# RFCS-RJ45_Foot_Pedal.net
KiCad netlist of a schematic drawn in EAGLE
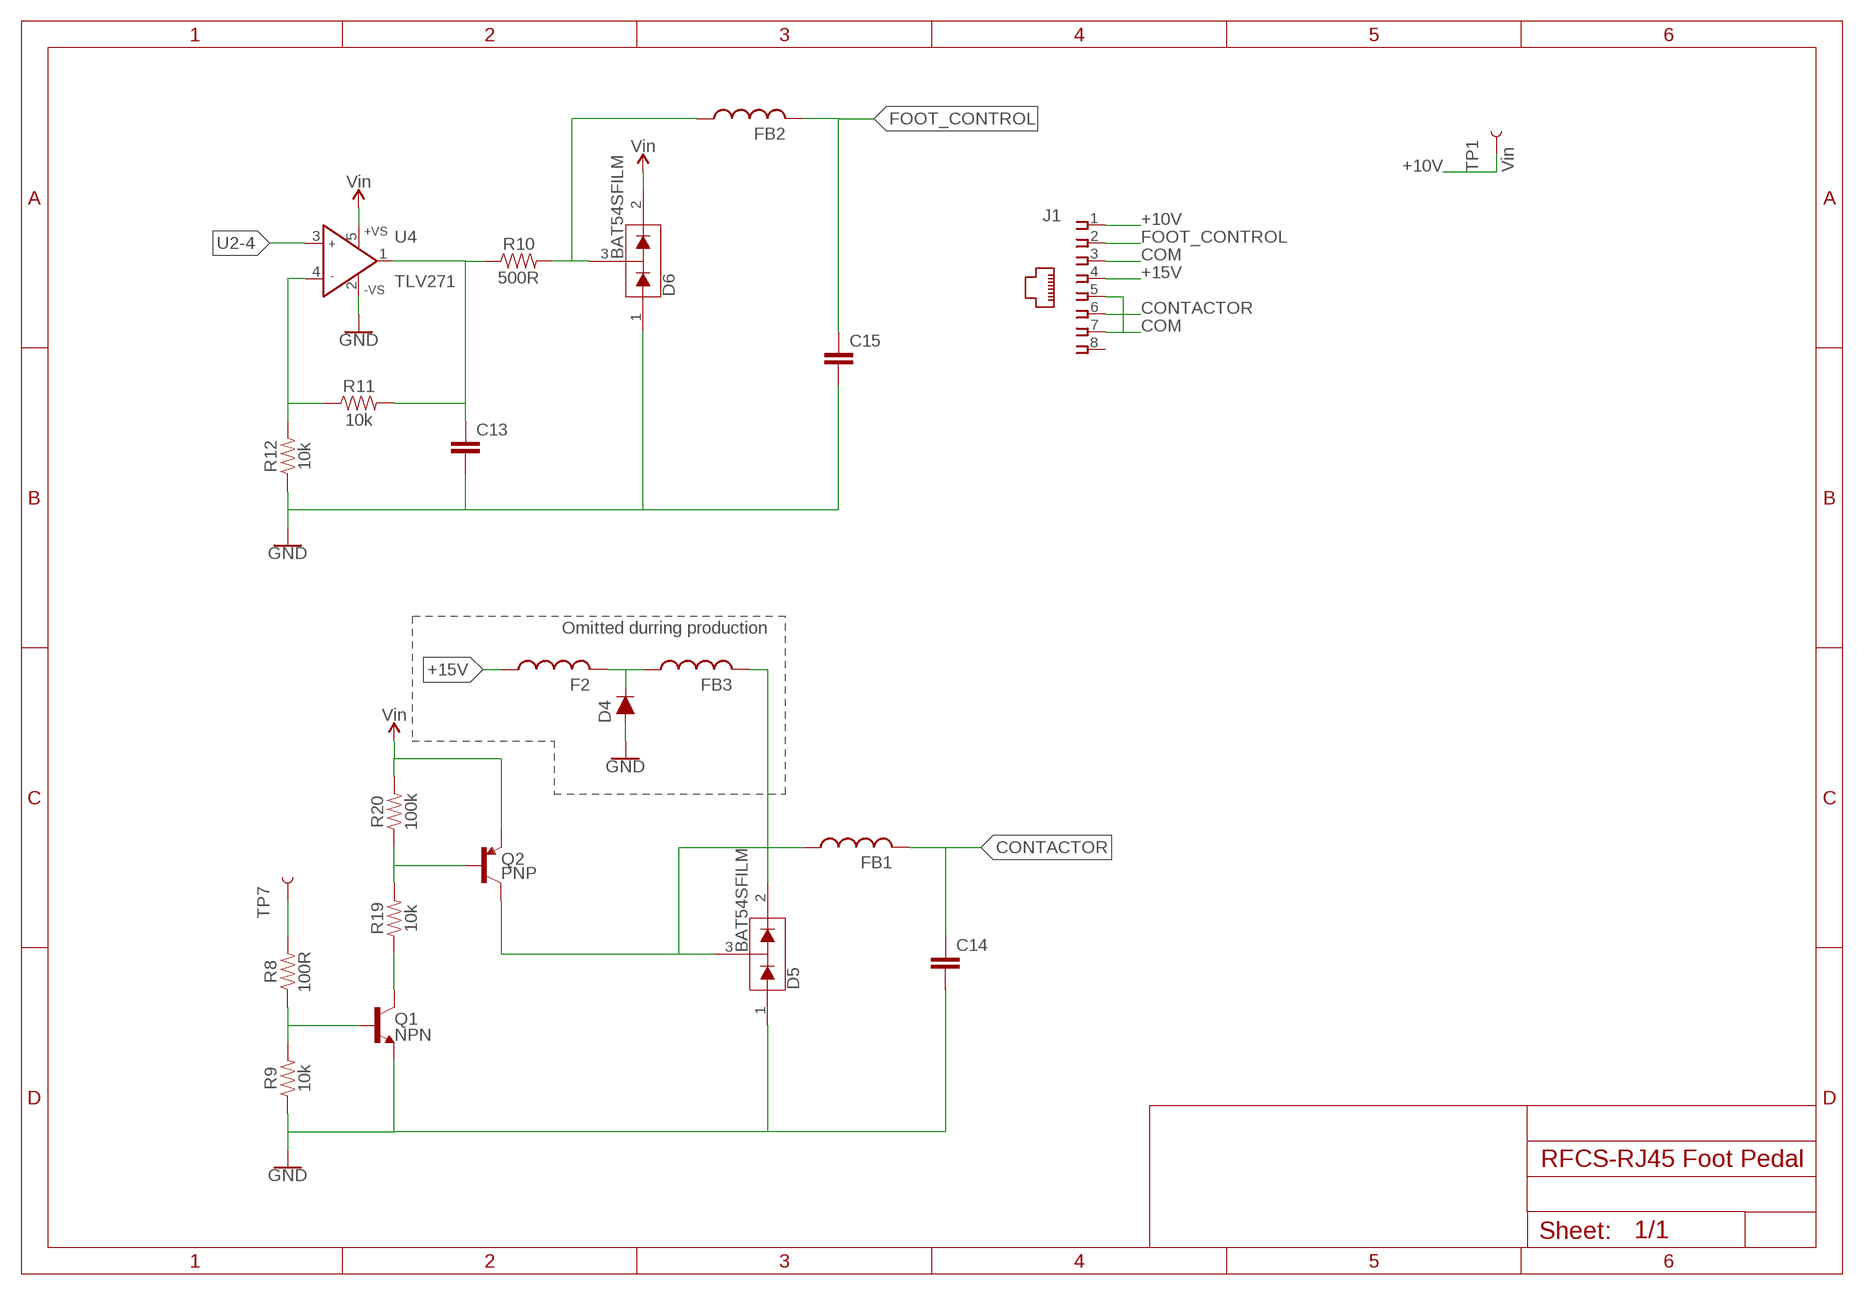
[diagram p0: schematic, sheet 1]

(export (version "E")
  (design (tool "Eeschema 10.0.6"))
  (components
    (comp (ref "C13")
      (value "C-EUC0402K")
      (footprint "eagle-import:C0402K")
      (libsource (lib "eagle-import") (part "C-EUC0402K"))
    )
    (comp (ref "C14")
      (value "C-EUC0402K")
      (footprint "eagle-import:C0402K")
      (libsource (lib "eagle-import") (part "C-EUC0402K"))
    )
    (comp (ref "C15")
      (value "C-EUC0402K")
      (footprint "eagle-import:C0402K")
      (libsource (lib "eagle-import") (part "C-EUC0402K"))
    )
    (comp (ref "D4")
      (value "DIODE-BAS16J")
      (footprint "eagle-import:SOD-323")
      (libsource (lib "eagle-import") (part "DIODE-BAS16J"))
    )
    (comp (ref "D5")
      (value "BAT54SFILM")
      (footprint "eagle-import:SOT23-3")
      (libsource (lib "eagle-import") (part "BAV99"))
    )
    (comp (ref "D6")
      (value "BAT54SFILM")
      (footprint "eagle-import:SOT23-3")
      (libsource (lib "eagle-import") (part "BAV99"))
    )
    (comp (ref "F2")
      (value "L-USL1812")
      (footprint "eagle-import:L1812")
      (libsource (lib "eagle-import") (part "L-USL1812"))
    )
    (comp (ref "FB1")
      (value "L-USL1812")
      (footprint "eagle-import:L1812")
      (libsource (lib "eagle-import") (part "L-USL1812"))
    )
    (comp (ref "FB2")
      (value "L-USL1812")
      (footprint "eagle-import:L1812")
      (libsource (lib "eagle-import") (part "L-USL1812"))
    )
    (comp (ref "FB3")
      (value "L-USL1812")
      (footprint "eagle-import:L1812")
      (libsource (lib "eagle-import") (part "L-USL1812"))
    )
    (comp (ref "J1")
      (value "0446200001")
      (footprint "eagle-import:0446200001")
      (fields (field (name "MF") "MOLEX"))
      (libsource (lib "eagle-import") (part "0446200001"))
    )
    (comp (ref "Q1")
      (value "NPN")
      (footprint "eagle-import:SOT23-3")
      (libsource (lib "eagle-import") (part "TRANS_NPN-MMBT2222AL"))
    )
    (comp (ref "Q2")
      (value "PNP")
      (footprint "eagle-import:SOT23-3")
      (libsource (lib "eagle-import") (part "TRANS_PNP-MMBT4403"))
    )
    (comp (ref "R8")
      (value "100R")
      (footprint "eagle-import:0603")
      (libsource (lib "eagle-import") (part "RESISTOR0603"))
    )
    (comp (ref "R9")
      (value "10k")
      (footprint "eagle-import:0603")
      (libsource (lib "eagle-import") (part "RESISTOR0603"))
    )
    (comp (ref "R10")
      (value "500R")
      (footprint "eagle-import:0603")
      (libsource (lib "eagle-import") (part "RESISTOR0603"))
    )
    (comp (ref "R11")
      (value "10k")
      (footprint "eagle-import:0603")
      (libsource (lib "eagle-import") (part "RESISTOR0603"))
    )
    (comp (ref "R12")
      (value "10k")
      (footprint "eagle-import:0603")
      (libsource (lib "eagle-import") (part "RESISTOR0603"))
    )
    (comp (ref "R19")
      (value "10k")
      (footprint "eagle-import:0603")
      (libsource (lib "eagle-import") (part "RESISTOR0603"))
    )
    (comp (ref "R20")
      (value "100k")
      (footprint "eagle-import:0603")
      (libsource (lib "eagle-import") (part "RESISTOR0603"))
    )
    (comp (ref "TP1")
      (value "Vin")
      (footprint "eagle-import:PAD.02X.02")
      (libsource (lib "eagle-import") (part "TEST-POINT2"))
    )
    (comp (ref "TP7")
      (value "TEST-POINT2")
      (footprint "eagle-import:PAD.02X.02")
      (libsource (lib "eagle-import") (part "TEST-POINT2"))
    )
    (comp (ref "U4")
      (value "TLV271")
      (footprint "eagle-import:SC70-5")
      (fields (field (name "MF") "ALTERA CORPORATION") (field (name "MPN") "AD8541AKSZ-REEL7"))
      (libsource (lib "eagle-import") (part "AD8541KS"))
    )
  )
  (nets
    (net (code "1") (name "+15V") (class "Default")
      (node (ref "F2") (pin "1") (pinfunction "1_1") (pintype "passive"))
      (node (ref "J1") (pin "4") (pinfunction "4_4") (pintype "passive"))
    )
    (net (code "2") (name "/+10V") (class "Default")
      (node (ref "J1") (pin "1") (pinfunction "1_1") (pintype "passive"))
      (node (ref "TP1") (pin "P$1") (pinfunction "1_P$1") (pintype "bidirectional"))
    )
    (net (code "3") (name "/COM") (class "Default")
      (node (ref "J1") (pin "3") (pinfunction "3_3") (pintype "passive"))
      (node (ref "J1") (pin "5") (pinfunction "5_5") (pintype "passive"))
      (node (ref "J1") (pin "7") (pinfunction "7_7") (pintype "passive"))
    )
    (net (code "4") (name "CONTACTOR") (class "Default")
      (node (ref "C14") (pin "1") (pinfunction "1_1") (pintype "passive"))
      (node (ref "FB1") (pin "2") (pinfunction "2_2") (pintype "passive"))
      (node (ref "J1") (pin "6") (pinfunction "6_6") (pintype "passive"))
    )
    (net (code "5") (name "FOOT_CONTROL") (class "Default")
      (node (ref "C15") (pin "1") (pinfunction "1_1") (pintype "passive"))
      (node (ref "FB2") (pin "2") (pinfunction "2_2") (pintype "passive"))
      (node (ref "J1") (pin "2") (pinfunction "2_2") (pintype "passive"))
    )
    (net (code "6") (name "GND") (class "Default")
      (node (ref "C13") (pin "2") (pinfunction "2_2") (pintype "passive"))
      (node (ref "C14") (pin "2") (pinfunction "2_2") (pintype "passive"))
      (node (ref "C15") (pin "2") (pinfunction "2_2") (pintype "passive"))
      (node (ref "D4") (pin "A") (pinfunction "A_A") (pintype "passive"))
      (node (ref "D5") (pin "1") (pinfunction "A1_1") (pintype "bidirectional"))
      (node (ref "D6") (pin "1") (pinfunction "A1_1") (pintype "bidirectional"))
      (node (ref "Q1") (pin "2") (pinfunction "E_2") (pintype "passive"))
      (node (ref "R12") (pin "1") (pinfunction "1_1") (pintype "passive"))
      (node (ref "R9") (pin "1") (pinfunction "1_1") (pintype "passive"))
      (node (ref "U4") (pin "2") (pinfunction "-VS_2") (pintype "input"))
    )
    (net (code "7") (name "Net-(D4-PadC)") (class "Default")
      (node (ref "D4") (pin "C") (pinfunction "C_C") (pintype "passive"))
      (node (ref "F2") (pin "2") (pinfunction "2_2") (pintype "passive"))
      (node (ref "FB3") (pin "1") (pinfunction "1_1") (pintype "passive"))
    )
    (net (code "8") (name "Net-(D5-C2)") (class "Default")
      (node (ref "D5") (pin "2") (pinfunction "C2_2") (pintype "bidirectional"))
      (node (ref "FB3") (pin "2") (pinfunction "2_2") (pintype "passive"))
    )
    (net (code "9") (name "Net-(D5-COM)") (class "Default")
      (node (ref "D5") (pin "3") (pinfunction "COM_3") (pintype "bidirectional"))
      (node (ref "FB1") (pin "1") (pinfunction "1_1") (pintype "passive"))
      (node (ref "Q2") (pin "3") (pinfunction "C_3") (pintype "passive"))
    )
    (net (code "10") (name "Net-(D6-COM)") (class "Default")
      (node (ref "D6") (pin "3") (pinfunction "COM_3") (pintype "bidirectional"))
      (node (ref "FB2") (pin "1") (pinfunction "1_1") (pintype "passive"))
      (node (ref "R10") (pin "2") (pinfunction "2_2") (pintype "passive"))
    )
    (net (code "11") (name "Net-(Q1-B)") (class "Default")
      (node (ref "Q1") (pin "1") (pinfunction "B_1") (pintype "passive"))
      (node (ref "R8") (pin "1") (pinfunction "1_1") (pintype "passive"))
      (node (ref "R9") (pin "2") (pinfunction "2_2") (pintype "passive"))
    )
    (net (code "12") (name "Net-(Q1-C)") (class "Default")
      (node (ref "Q1") (pin "3") (pinfunction "C_3") (pintype "passive"))
      (node (ref "R19") (pin "1") (pinfunction "1_1") (pintype "passive"))
    )
    (net (code "13") (name "Net-(Q2-B)") (class "Default")
      (node (ref "Q2") (pin "1") (pinfunction "B_1") (pintype "passive"))
      (node (ref "R19") (pin "2") (pinfunction "2_2") (pintype "passive"))
      (node (ref "R20") (pin "1") (pinfunction "1_1") (pintype "passive"))
    )
    (net (code "14") (name "Net-(TP7-1)") (class "Default")
      (node (ref "R8") (pin "2") (pinfunction "2_2") (pintype "passive"))
      (node (ref "TP7") (pin "P$1") (pinfunction "1_P$1") (pintype "bidirectional"))
    )
    (net (code "15") (name "Net-(U4-IN-)") (class "Default")
      (node (ref "R11") (pin "1") (pinfunction "1_1") (pintype "passive"))
      (node (ref "R12") (pin "2") (pinfunction "2_2") (pintype "passive"))
      (node (ref "U4") (pin "4") (pinfunction "IN-_4") (pintype "input"))
    )
    (net (code "16") (name "Net-(U4-OUT)") (class "Default")
      (node (ref "C13") (pin "1") (pinfunction "1_1") (pintype "passive"))
      (node (ref "R10") (pin "1") (pinfunction "1_1") (pintype "passive"))
      (node (ref "R11") (pin "2") (pinfunction "2_2") (pintype "passive"))
      (node (ref "U4") (pin "1") (pinfunction "OUT_1") (pintype "output"))
    )
    (net (code "17") (name "U2-4") (class "Default")
      (node (ref "U4") (pin "3") (pinfunction "IN+_3") (pintype "input"))
    )
    (net (code "18") (name "Vin") (class "Default")
      (node (ref "D6") (pin "2") (pinfunction "C2_2") (pintype "bidirectional"))
      (node (ref "Q2") (pin "2") (pinfunction "E_2") (pintype "passive"))
      (node (ref "R20") (pin "2") (pinfunction "2_2") (pintype "passive"))
      (node (ref "U4") (pin "5") (pinfunction "+VS_5") (pintype "input"))
    )
    (net (code "19") (name "unconnected-(J1-Pad8)") (class "Default")
      (node (ref "J1") (pin "8") (pinfunction "8_8") (pintype "passive"))
    )
  )
)
